# M117Z.net
KiCad netlist of a schematic drawn in Altium Designer
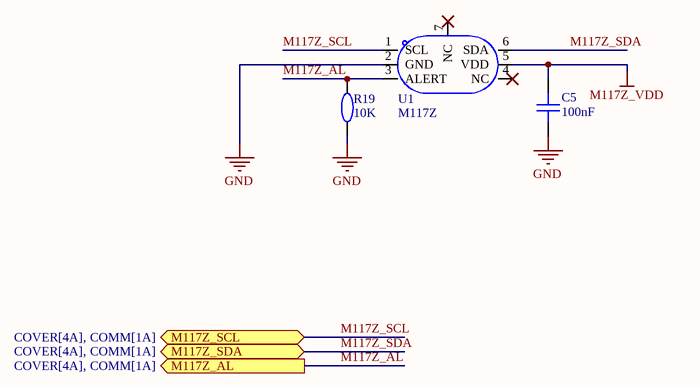
[diagram p0: M117Z.SchDoc]

(export (version "E")
  (design (tool "Eeschema 10.0.6"))
  (components
    (comp (ref "C5")
      (value "100nF")
      (footprint "C0402")
      (fields (field (name "NAME") "100nF"))
      (libsource (lib "my_library") (part "CAP_0402"))
    )
    (comp (ref "R19")
      (value "10K")
      (footprint "R0402")
      (fields (field (name "NAME") "10K"))
      (libsource (lib "my_library") (part "Res_0402"))
    )
    (comp (ref "U1")
      (value "M117Z")
      (footprint "TDFN-6_L2.0-W2.0-P0.65-TL-EP1.4")
      (fields
        (field (name "MANUFACTURER") "Mysentech(敏源传感)")
        (field (name "TOLERANCE") "±0.1℃")
        (field (name "NAME") "M117Z")
      )
      (libsource (lib "my_library") (part "M117Z"))
    )
  )
  (nets
    (net (code "1") (name "/M117Z_AL") (class "Default")
      (node (ref "R19") (pin "2") (pinfunction "2_2") (pintype "passive"))
      (node (ref "U1") (pin "3") (pinfunction "ALERT_3") (pintype "passive"))
    )
    (net (code "2") (name "/M117Z_SCL") (class "Default")
      (node (ref "U1") (pin "1") (pinfunction "SCL_1") (pintype "passive"))
    )
    (net (code "3") (name "/M117Z_SDA") (class "Default")
      (node (ref "U1") (pin "6") (pinfunction "SDA_6") (pintype "passive"))
    )
    (net (code "4") (name "GND") (class "Default")
      (node (ref "C5") (pin "1") (pinfunction "1_1") (pintype "passive"))
      (node (ref "R19") (pin "1") (pinfunction "1_1") (pintype "passive"))
      (node (ref "U1") (pin "2") (pinfunction "GND_2") (pintype "passive"))
    )
    (net (code "5") (name "M117Z_VDD") (class "Default")
      (node (ref "C5") (pin "2") (pinfunction "2_2") (pintype "passive"))
      (node (ref "U1") (pin "5") (pinfunction "VDD_5") (pintype "passive"))
    )
    (net (code "6") (name "unconnected-(U1-NC-Pad4)") (class "Default")
      (node (ref "U1") (pin "4") (pinfunction "NC_4") (pintype "passive+no_connect"))
    )
    (net (code "7") (name "unconnected-(U1-NC-Pad7)") (class "Default")
      (node (ref "U1") (pin "7") (pinfunction "NC_7") (pintype "passive+no_connect"))
    )
  )
)
